# emitter.net
KiCad netlist of a schematic drawn in Altium Designer
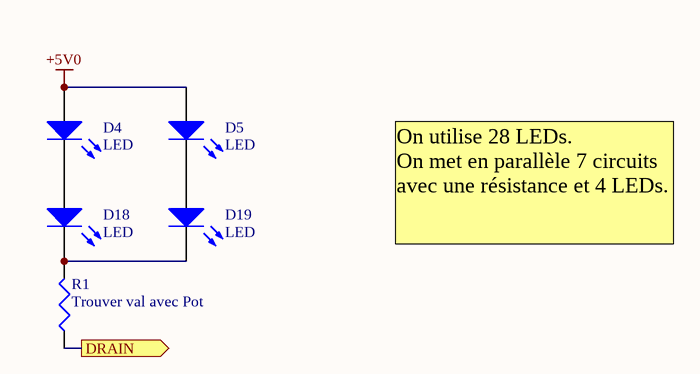
[diagram p0: emitter.SchDoc]

(export (version "E")
  (design (tool "Eeschema 10.0.6"))
  (components
    (comp (ref "D4")
      (value "LED")
      (footprint "LED 5MM Horiz")
      (description "Typical RED, GREEN, YELLOW, AMBER GaAs LED")
      (fields (field (name "PUBLISHER") "Altium Limited"))
      (libsource (lib "7Robot") (part "LED"))
    )
    (comp (ref "D5")
      (value "LED")
      (footprint "LED 5MM Horiz")
      (description "Typical RED, GREEN, YELLOW, AMBER GaAs LED")
      (fields (field (name "PUBLISHER") "Altium Limited"))
      (libsource (lib "7Robot") (part "LED"))
    )
    (comp (ref "D18")
      (value "LED")
      (footprint "LED 5MM Horiz")
      (description "Typical RED, GREEN, YELLOW, AMBER GaAs LED")
      (fields (field (name "PUBLISHER") "Altium Limited"))
      (libsource (lib "7Robot") (part "LED"))
    )
    (comp (ref "D19")
      (value "LED")
      (footprint "LED 5MM Horiz")
      (description "Typical RED, GREEN, YELLOW, AMBER GaAs LED")
      (fields (field (name "PUBLISHER") "Altium Limited"))
      (libsource (lib "7Robot") (part "LED"))
    )
    (comp (ref "R1")
      (value "Trouver val avec Pot")
      (footprint "AXIAL0.8 Vert")
      (description "Resistor")
      (fields (field (name "Comment") "RES") (field (name "PUBLISHER") "Altium Limited"))
      (libsource (lib "7Robot") (part "RES"))
    )
  )
  (nets
    (net (code "1") (name "+5V0") (class "Default")
      (node (ref "D4") (pin "A") (pinfunction "A_A") (pintype "passive"))
      (node (ref "D5") (pin "A") (pinfunction "A_A") (pintype "passive"))
    )
    (net (code "2") (name "/DRAIN") (class "Default")
      (node (ref "R1") (pin "1") (pinfunction "1_1") (pintype "passive"))
    )
    (net (code "3") (name "Net-(D18-PadA)") (class "Default")
      (node (ref "D18") (pin "A") (pinfunction "A_A") (pintype "passive"))
      (node (ref "D4") (pin "K") (pinfunction "K_K") (pintype "passive"))
    )
    (net (code "4") (name "Net-(D18-PadK)") (class "Default")
      (node (ref "D18") (pin "K") (pinfunction "K_K") (pintype "passive"))
      (node (ref "D19") (pin "K") (pinfunction "K_K") (pintype "passive"))
      (node (ref "R1") (pin "2") (pinfunction "2_2") (pintype "passive"))
    )
    (net (code "5") (name "Net-(D19-PadA)") (class "Default")
      (node (ref "D19") (pin "A") (pinfunction "A_A") (pintype "passive"))
      (node (ref "D5") (pin "K") (pinfunction "K_K") (pintype "passive"))
    )
  )
)
